# schem2.net
KiCad netlist of a schematic drawn in EAGLE
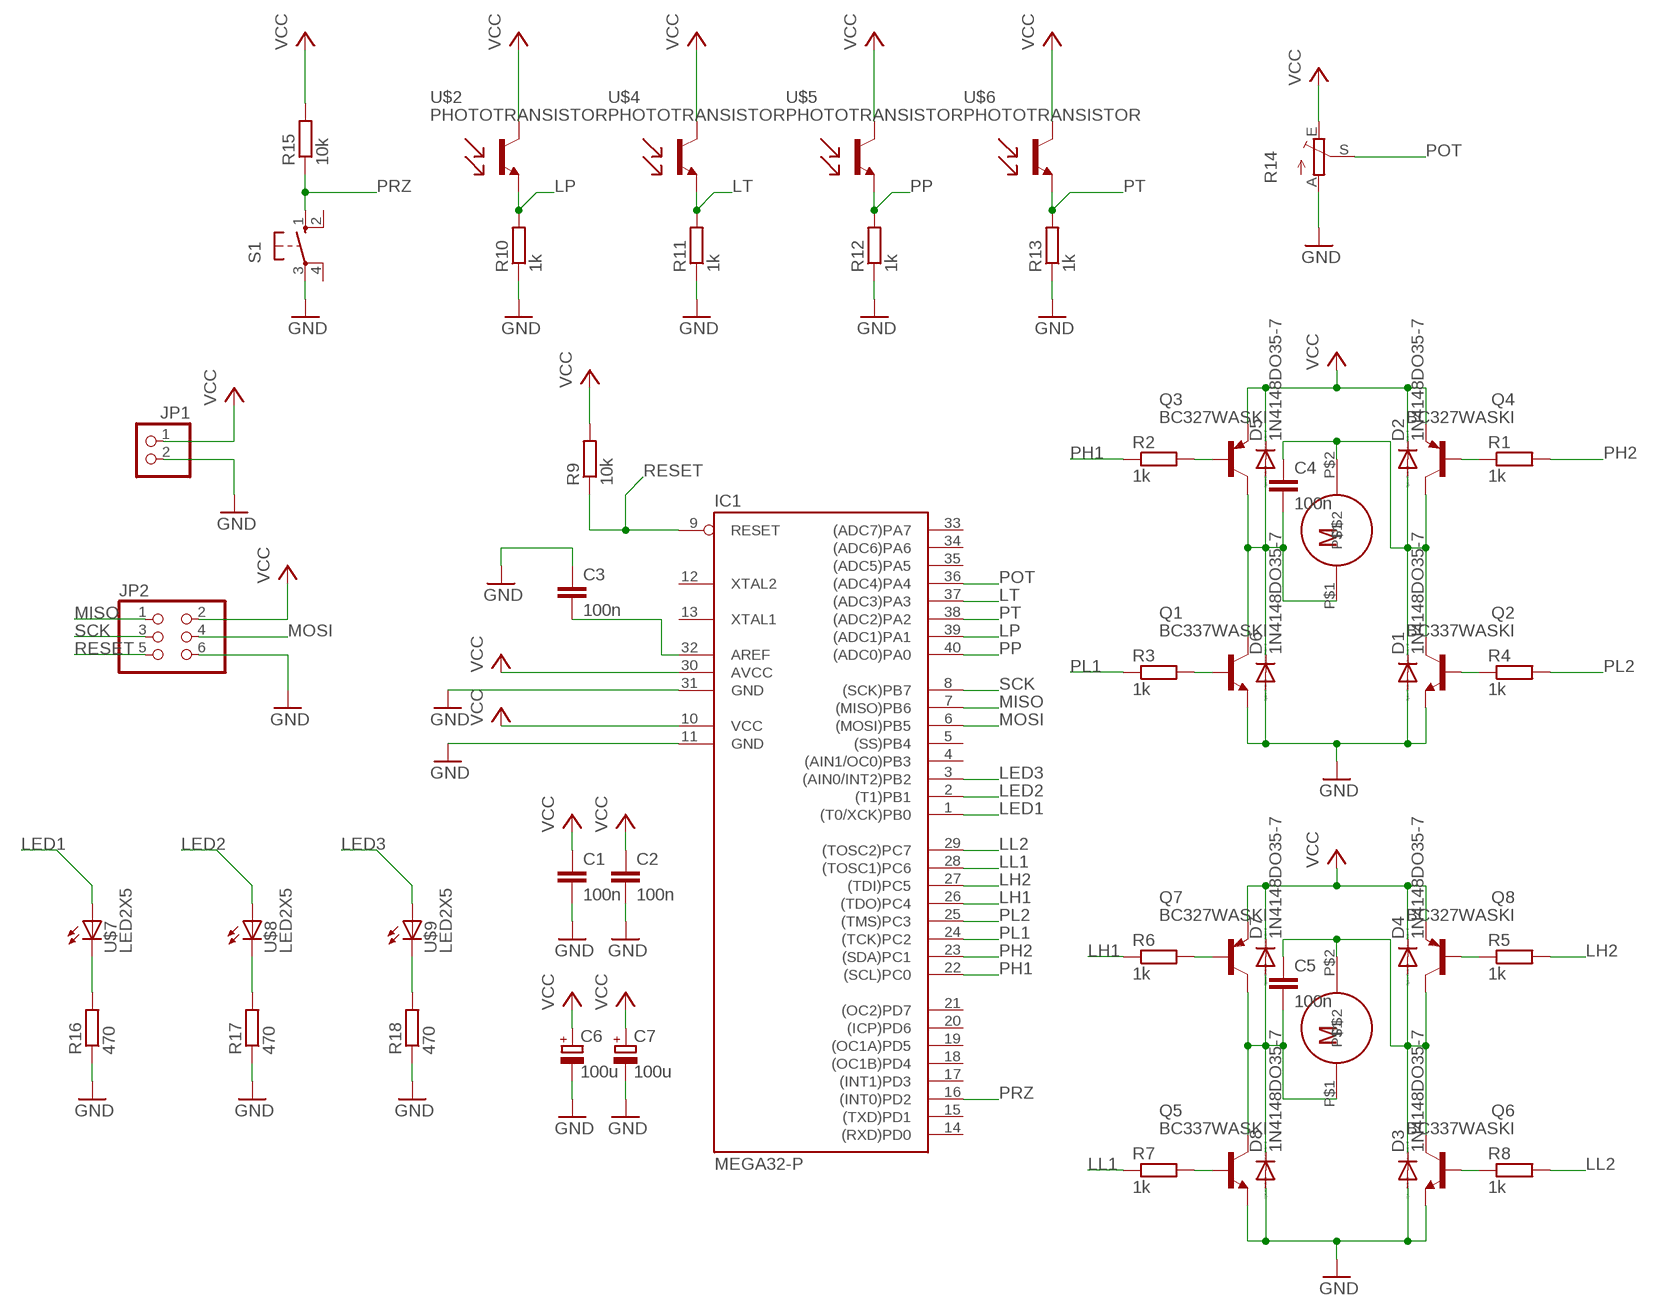
[diagram p0: schematic, sheet 1]

(export (version "E")
  (design (tool "Eeschema 10.0.6"))
  (components
    (comp (ref "C1")
      (value "100n")
      (footprint "eagle-import:C025-025X050")
      (libsource (lib "eagle-import") (part "C-EU025-025X050"))
    )
    (comp (ref "C2")
      (value "100n")
      (footprint "eagle-import:C025-025X050")
      (libsource (lib "eagle-import") (part "C-EU025-025X050"))
    )
    (comp (ref "C3")
      (value "100n")
      (footprint "eagle-import:C025-025X050")
      (libsource (lib "eagle-import") (part "C-EU025-025X050"))
    )
    (comp (ref "C4")
      (value "100n")
      (footprint "eagle-import:C025-025X050")
      (libsource (lib "eagle-import") (part "C-EU025-025X050"))
    )
    (comp (ref "C5")
      (value "100n")
      (footprint "eagle-import:C025-025X050")
      (libsource (lib "eagle-import") (part "C-EU025-025X050"))
    )
    (comp (ref "C6")
      (value "100u")
      (footprint "eagle-import:E2-5")
      (libsource (lib "eagle-import") (part "CPOL-EUE2-5"))
    )
    (comp (ref "C7")
      (value "100u")
      (footprint "eagle-import:E2-5")
      (libsource (lib "eagle-import") (part "CPOL-EUE2-5"))
    )
    (comp (ref "D1")
      (value "1N4148DO35-7")
      (footprint "eagle-import:DO35-7")
      (libsource (lib "eagle-import") (part "1N4148DO35-7"))
    )
    (comp (ref "D2")
      (value "1N4148DO35-7")
      (footprint "eagle-import:DO35-7")
      (libsource (lib "eagle-import") (part "1N4148DO35-7"))
    )
    (comp (ref "D3")
      (value "1N4148DO35-7")
      (footprint "eagle-import:DO35-7")
      (libsource (lib "eagle-import") (part "1N4148DO35-7"))
    )
    (comp (ref "D4")
      (value "1N4148DO35-7")
      (footprint "eagle-import:DO35-7")
      (libsource (lib "eagle-import") (part "1N4148DO35-7"))
    )
    (comp (ref "D5")
      (value "1N4148DO35-7")
      (footprint "eagle-import:DO35-7")
      (libsource (lib "eagle-import") (part "1N4148DO35-7"))
    )
    (comp (ref "D6")
      (value "1N4148DO35-7")
      (footprint "eagle-import:DO35-7")
      (libsource (lib "eagle-import") (part "1N4148DO35-7"))
    )
    (comp (ref "D7")
      (value "1N4148DO35-7")
      (footprint "eagle-import:DO35-7")
      (libsource (lib "eagle-import") (part "1N4148DO35-7"))
    )
    (comp (ref "D8")
      (value "1N4148DO35-7")
      (footprint "eagle-import:DO35-7")
      (libsource (lib "eagle-import") (part "1N4148DO35-7"))
    )
    (comp (ref "IC1")
      (value "MEGA32-P")
      (footprint "eagle-import:DIL40")
      (fields (field (name "MPN") "ATMEGA32-16PU"))
      (libsource (lib "eagle-import") (part "MEGA32-P"))
    )
    (comp (ref "JP1")
      (value "PINHD-1X2")
      (footprint "eagle-import:1X02")
      (libsource (lib "eagle-import") (part "PINHD-1X2"))
    )
    (comp (ref "JP2")
      (value "PINHD-2X3")
      (footprint "eagle-import:2X03")
      (libsource (lib "eagle-import") (part "PINHD-2X3"))
    )
    (comp (ref "Q1")
      (value "BC337WASKI")
      (footprint "eagle-import:TO92-WASKI")
      (libsource (lib "eagle-import") (part "BC337WASKI"))
    )
    (comp (ref "Q2")
      (value "BC337WASKI")
      (footprint "eagle-import:TO92-WASKI")
      (libsource (lib "eagle-import") (part "BC337WASKI"))
    )
    (comp (ref "Q3")
      (value "BC327WASKI")
      (footprint "eagle-import:TO92-WASKI")
      (libsource (lib "eagle-import") (part "BC327WASKI"))
    )
    (comp (ref "Q4")
      (value "BC327WASKI")
      (footprint "eagle-import:TO92-WASKI")
      (libsource (lib "eagle-import") (part "BC327WASKI"))
    )
    (comp (ref "Q5")
      (value "BC337WASKI")
      (footprint "eagle-import:TO92-WASKI")
      (libsource (lib "eagle-import") (part "BC337WASKI"))
    )
    (comp (ref "Q6")
      (value "BC337WASKI")
      (footprint "eagle-import:TO92-WASKI")
      (libsource (lib "eagle-import") (part "BC337WASKI"))
    )
    (comp (ref "Q7")
      (value "BC327WASKI")
      (footprint "eagle-import:TO92-WASKI")
      (libsource (lib "eagle-import") (part "BC327WASKI"))
    )
    (comp (ref "Q8")
      (value "BC327WASKI")
      (footprint "eagle-import:TO92-WASKI")
      (libsource (lib "eagle-import") (part "BC327WASKI"))
    )
    (comp (ref "R1")
      (value "1k")
      (footprint "eagle-import:0207_7")
      (libsource (lib "eagle-import") (part "R-EU_0207/7"))
    )
    (comp (ref "R2")
      (value "1k")
      (footprint "eagle-import:0207_7")
      (libsource (lib "eagle-import") (part "R-EU_0207/7"))
    )
    (comp (ref "R3")
      (value "1k")
      (footprint "eagle-import:0207_7")
      (libsource (lib "eagle-import") (part "R-EU_0207/7"))
    )
    (comp (ref "R4")
      (value "1k")
      (footprint "eagle-import:0207_7")
      (libsource (lib "eagle-import") (part "R-EU_0207/7"))
    )
    (comp (ref "R5")
      (value "1k")
      (footprint "eagle-import:0207_7")
      (libsource (lib "eagle-import") (part "R-EU_0207/7"))
    )
    (comp (ref "R6")
      (value "1k")
      (footprint "eagle-import:0207_7")
      (libsource (lib "eagle-import") (part "R-EU_0207/7"))
    )
    (comp (ref "R7")
      (value "1k")
      (footprint "eagle-import:0207_7")
      (libsource (lib "eagle-import") (part "R-EU_0207/7"))
    )
    (comp (ref "R8")
      (value "1k")
      (footprint "eagle-import:0207_7")
      (libsource (lib "eagle-import") (part "R-EU_0207/7"))
    )
    (comp (ref "R9")
      (value "10k")
      (footprint "eagle-import:0207_7")
      (libsource (lib "eagle-import") (part "R-EU_0207/7"))
    )
    (comp (ref "R10")
      (value "1k")
      (footprint "eagle-import:0207_7")
      (libsource (lib "eagle-import") (part "R-EU_0207/7"))
    )
    (comp (ref "R11")
      (value "1k")
      (footprint "eagle-import:0207_7")
      (libsource (lib "eagle-import") (part "R-EU_0207/7"))
    )
    (comp (ref "R12")
      (value "1k")
      (footprint "eagle-import:0207_7")
      (libsource (lib "eagle-import") (part "R-EU_0207/7"))
    )
    (comp (ref "R13")
      (value "1k")
      (footprint "eagle-import:0207_7")
      (libsource (lib "eagle-import") (part "R-EU_0207/7"))
    )
    (comp (ref "R14")
      (value "TRIM_EU-B64Y")
      (footprint "eagle-import:B64Y")
      (libsource (lib "eagle-import") (part "TRIM_EU-B64Y"))
    )
    (comp (ref "R15")
      (value "10k")
      (footprint "eagle-import:0207_7")
      (libsource (lib "eagle-import") (part "R-EU_0207/7"))
    )
    (comp (ref "R16")
      (value "470")
      (footprint "eagle-import:0207_7")
      (libsource (lib "eagle-import") (part "R-EU_0207/7"))
    )
    (comp (ref "R17")
      (value "470")
      (footprint "eagle-import:0207_7")
      (libsource (lib "eagle-import") (part "R-EU_0207/7"))
    )
    (comp (ref "R18")
      (value "470")
      (footprint "eagle-import:0207_7")
      (libsource (lib "eagle-import") (part "R-EU_0207/7"))
    )
    (comp (ref "S1")
      (value "10-XX")
      (footprint "eagle-import:B3F-10XX")
      (fields (field (name "MPN") "B3F-1000"))
      (libsource (lib "eagle-import") (part "10-XX"))
    )
    (comp (ref "U$1")
      (value "DG02S")
      (footprint "eagle-import:DG02S")
      (libsource (lib "eagle-import") (part "DG02S"))
    )
    (comp (ref "U$2")
      (value "PHOTOTRANSISTOR")
      (footprint "eagle-import:PHOTOTRANSISTOR")
      (libsource (lib "eagle-import") (part "PHOTOTRANSISTOR"))
    )
    (comp (ref "U$3")
      (value "DG02S")
      (footprint "eagle-import:DG02S")
      (libsource (lib "eagle-import") (part "DG02S"))
    )
    (comp (ref "U$4")
      (value "PHOTOTRANSISTOR")
      (footprint "eagle-import:PHOTOTRANSISTOR")
      (libsource (lib "eagle-import") (part "PHOTOTRANSISTOR"))
    )
    (comp (ref "U$5")
      (value "PHOTOTRANSISTOR")
      (footprint "eagle-import:PHOTOTRANSISTOR")
      (libsource (lib "eagle-import") (part "PHOTOTRANSISTOR"))
    )
    (comp (ref "U$6")
      (value "PHOTOTRANSISTOR")
      (footprint "eagle-import:PHOTOTRANSISTOR")
      (libsource (lib "eagle-import") (part "PHOTOTRANSISTOR"))
    )
    (comp (ref "U$7")
      (value "LED2X5")
      (footprint "eagle-import:LED3MM")
      (libsource (lib "eagle-import") (part "LED2X5"))
    )
    (comp (ref "U$8")
      (value "LED2X5")
      (footprint "eagle-import:LED3MM")
      (libsource (lib "eagle-import") (part "LED2X5"))
    )
    (comp (ref "U$9")
      (value "LED2X5")
      (footprint "eagle-import:LED3MM")
      (libsource (lib "eagle-import") (part "LED2X5"))
    )
  )
  (nets
    (net (code "1") (name "/LED1") (class "Default")
      (node (ref "IC1") (pin "1") (pinfunction "(T0/XCK)PB0_1") (pintype "bidirectional"))
      (node (ref "U$7") (pin "A") (pinfunction "A_A") (pintype "passive"))
    )
    (net (code "2") (name "/LED2") (class "Default")
      (node (ref "IC1") (pin "2") (pinfunction "(T1)PB1_2") (pintype "bidirectional"))
      (node (ref "U$8") (pin "A") (pinfunction "A_A") (pintype "passive"))
    )
    (net (code "3") (name "/LED3") (class "Default")
      (node (ref "IC1") (pin "3") (pinfunction "(AIN0/INT2)PB2_3") (pintype "bidirectional"))
      (node (ref "U$9") (pin "A") (pinfunction "A_A") (pintype "passive"))
    )
    (net (code "4") (name "/LH1") (class "Default")
      (node (ref "IC1") (pin "26") (pinfunction "(TDO)PC4_26") (pintype "bidirectional"))
      (node (ref "R6") (pin "1") (pinfunction "1_1") (pintype "passive"))
    )
    (net (code "5") (name "/LH2") (class "Default")
      (node (ref "IC1") (pin "27") (pinfunction "(TDI)PC5_27") (pintype "bidirectional"))
      (node (ref "R5") (pin "2") (pinfunction "2_2") (pintype "passive"))
    )
    (net (code "6") (name "/LL1") (class "Default")
      (node (ref "IC1") (pin "28") (pinfunction "(TOSC1)PC6_28") (pintype "bidirectional"))
      (node (ref "R7") (pin "1") (pinfunction "1_1") (pintype "passive"))
    )
    (net (code "7") (name "/LL2") (class "Default")
      (node (ref "IC1") (pin "29") (pinfunction "(TOSC2)PC7_29") (pintype "bidirectional"))
      (node (ref "R8") (pin "2") (pinfunction "2_2") (pintype "passive"))
    )
    (net (code "8") (name "/LP") (class "Default")
      (node (ref "IC1") (pin "39") (pinfunction "(ADC1)PA1_39") (pintype "bidirectional"))
      (node (ref "R10") (pin "2") (pinfunction "2_2") (pintype "passive"))
      (node (ref "U$2") (pin "E") (pinfunction "E_E") (pintype "passive"))
    )
    (net (code "9") (name "/LT") (class "Default")
      (node (ref "IC1") (pin "37") (pinfunction "(ADC3)PA3_37") (pintype "bidirectional"))
      (node (ref "R11") (pin "2") (pinfunction "2_2") (pintype "passive"))
      (node (ref "U$4") (pin "E") (pinfunction "E_E") (pintype "passive"))
    )
    (net (code "10") (name "/MISO") (class "Default")
      (node (ref "IC1") (pin "7") (pinfunction "(MISO)PB6_7") (pintype "bidirectional"))
      (node (ref "JP2") (pin "1") (pinfunction "1_1") (pintype "passive"))
    )
    (net (code "11") (name "/MOSI") (class "Default")
      (node (ref "IC1") (pin "6") (pinfunction "(MOSI)PB5_6") (pintype "bidirectional"))
      (node (ref "JP2") (pin "4") (pinfunction "4_4") (pintype "passive"))
    )
    (net (code "12") (name "/PH1") (class "Default")
      (node (ref "IC1") (pin "22") (pinfunction "(SCL)PC0_22") (pintype "bidirectional"))
      (node (ref "R2") (pin "1") (pinfunction "1_1") (pintype "passive"))
    )
    (net (code "13") (name "/PH2") (class "Default")
      (node (ref "IC1") (pin "23") (pinfunction "(SDA)PC1_23") (pintype "bidirectional"))
      (node (ref "R1") (pin "2") (pinfunction "2_2") (pintype "passive"))
    )
    (net (code "14") (name "/PL1") (class "Default")
      (node (ref "IC1") (pin "24") (pinfunction "(TCK)PC2_24") (pintype "bidirectional"))
      (node (ref "R3") (pin "1") (pinfunction "1_1") (pintype "passive"))
    )
    (net (code "15") (name "/PL2") (class "Default")
      (node (ref "IC1") (pin "25") (pinfunction "(TMS)PC3_25") (pintype "bidirectional"))
      (node (ref "R4") (pin "2") (pinfunction "2_2") (pintype "passive"))
    )
    (net (code "16") (name "/POT") (class "Default")
      (node (ref "IC1") (pin "36") (pinfunction "(ADC4)PA4_36") (pintype "bidirectional"))
      (node (ref "R14") (pin "S") (pinfunction "S_S") (pintype "passive"))
    )
    (net (code "17") (name "/PP") (class "Default")
      (node (ref "IC1") (pin "40") (pinfunction "(ADC0)PA0_40") (pintype "bidirectional"))
      (node (ref "R12") (pin "2") (pinfunction "2_2") (pintype "passive"))
      (node (ref "U$5") (pin "E") (pinfunction "E_E") (pintype "passive"))
    )
    (net (code "18") (name "/PRZ") (class "Default")
      (node (ref "IC1") (pin "16") (pinfunction "(INT0)PD2_16") (pintype "bidirectional"))
      (node (ref "R15") (pin "1") (pinfunction "1_1") (pintype "passive"))
      (node (ref "S1") (pin "1") (pinfunction "S_1") (pintype "passive"))
    )
    (net (code "19") (name "/PT") (class "Default")
      (node (ref "IC1") (pin "38") (pinfunction "(ADC2)PA2_38") (pintype "bidirectional"))
      (node (ref "R13") (pin "2") (pinfunction "2_2") (pintype "passive"))
      (node (ref "U$6") (pin "E") (pinfunction "E_E") (pintype "passive"))
    )
    (net (code "20") (name "/RESET") (class "Default")
      (node (ref "IC1") (pin "9") (pinfunction "RESET_9") (pintype "input"))
      (node (ref "JP2") (pin "5") (pinfunction "5_5") (pintype "passive"))
      (node (ref "R9") (pin "1") (pinfunction "1_1") (pintype "passive"))
    )
    (net (code "21") (name "/SCK") (class "Default")
      (node (ref "IC1") (pin "8") (pinfunction "(SCK)PB7_8") (pintype "bidirectional"))
      (node (ref "JP2") (pin "3") (pinfunction "3_3") (pintype "passive"))
    )
    (net (code "22") (name "GND") (class "Default")
      (node (ref "C1") (pin "2") (pinfunction "2_2") (pintype "passive"))
      (node (ref "C2") (pin "2") (pinfunction "2_2") (pintype "passive"))
      (node (ref "C3") (pin "1") (pinfunction "1_1") (pintype "passive"))
      (node (ref "C6") (pin "-") (pinfunction "-_-") (pintype "passive"))
      (node (ref "C7") (pin "-") (pinfunction "-_-") (pintype "passive"))
      (node (ref "D1") (pin "A") (pinfunction "A_A") (pintype "passive"))
      (node (ref "D3") (pin "A") (pinfunction "A_A") (pintype "passive"))
      (node (ref "D6") (pin "A") (pinfunction "A_A") (pintype "passive"))
      (node (ref "D8") (pin "A") (pinfunction "A_A") (pintype "passive"))
      (node (ref "IC1") (pin "11") (pinfunction "GND_11") (pintype "power_in"))
      (node (ref "IC1") (pin "31") (pinfunction "GND_31") (pintype "power_in"))
      (node (ref "JP1") (pin "2") (pinfunction "2_2") (pintype "passive"))
      (node (ref "JP2") (pin "6") (pinfunction "6_6") (pintype "passive"))
      (node (ref "Q1") (pin "E") (pinfunction "E_E") (pintype "passive"))
      (node (ref "Q2") (pin "E") (pinfunction "E_E") (pintype "passive"))
      (node (ref "Q5") (pin "E") (pinfunction "E_E") (pintype "passive"))
      (node (ref "Q6") (pin "E") (pinfunction "E_E") (pintype "passive"))
      (node (ref "R10") (pin "1") (pinfunction "1_1") (pintype "passive"))
      (node (ref "R11") (pin "1") (pinfunction "1_1") (pintype "passive"))
      (node (ref "R12") (pin "1") (pinfunction "1_1") (pintype "passive"))
      (node (ref "R13") (pin "1") (pinfunction "1_1") (pintype "passive"))
      (node (ref "R14") (pin "A") (pinfunction "A_A") (pintype "passive"))
      (node (ref "R16") (pin "1") (pinfunction "1_1") (pintype "passive"))
      (node (ref "R17") (pin "1") (pinfunction "1_1") (pintype "passive"))
      (node (ref "R18") (pin "1") (pinfunction "1_1") (pintype "passive"))
      (node (ref "S1") (pin "3") (pinfunction "P_3") (pintype "passive"))
    )
    (net (code "23") (name "Net-(C4-Pad1)") (class "Default")
      (node (ref "C4") (pin "1") (pinfunction "1_1") (pintype "passive"))
      (node (ref "D1") (pin "C") (pinfunction "C_C") (pintype "passive"))
      (node (ref "D2") (pin "A") (pinfunction "A_A") (pintype "passive"))
      (node (ref "Q2") (pin "C") (pinfunction "C_C") (pintype "passive"))
      (node (ref "Q4") (pin "C") (pinfunction "C_C") (pintype "passive"))
      (node (ref "U$1") (pin "P$2") (pinfunction "P$2_P$2") (pintype "bidirectional"))
    )
    (net (code "24") (name "Net-(C4-Pad2)") (class "Default")
      (node (ref "C4") (pin "2") (pinfunction "2_2") (pintype "passive"))
      (node (ref "D5") (pin "A") (pinfunction "A_A") (pintype "passive"))
      (node (ref "D6") (pin "C") (pinfunction "C_C") (pintype "passive"))
      (node (ref "Q1") (pin "C") (pinfunction "C_C") (pintype "passive"))
      (node (ref "Q3") (pin "C") (pinfunction "C_C") (pintype "passive"))
      (node (ref "U$1") (pin "P$1") (pinfunction "P$1_P$1") (pintype "bidirectional"))
    )
    (net (code "25") (name "Net-(C5-Pad1)") (class "Default")
      (node (ref "C5") (pin "1") (pinfunction "1_1") (pintype "passive"))
      (node (ref "D3") (pin "C") (pinfunction "C_C") (pintype "passive"))
      (node (ref "D4") (pin "A") (pinfunction "A_A") (pintype "passive"))
      (node (ref "Q6") (pin "C") (pinfunction "C_C") (pintype "passive"))
      (node (ref "Q8") (pin "C") (pinfunction "C_C") (pintype "passive"))
      (node (ref "U$3") (pin "P$2") (pinfunction "P$2_P$2") (pintype "bidirectional"))
    )
    (net (code "26") (name "Net-(C5-Pad2)") (class "Default")
      (node (ref "C5") (pin "2") (pinfunction "2_2") (pintype "passive"))
      (node (ref "D7") (pin "A") (pinfunction "A_A") (pintype "passive"))
      (node (ref "D8") (pin "C") (pinfunction "C_C") (pintype "passive"))
      (node (ref "Q5") (pin "C") (pinfunction "C_C") (pintype "passive"))
      (node (ref "Q7") (pin "C") (pinfunction "C_C") (pintype "passive"))
      (node (ref "U$3") (pin "P$1") (pinfunction "P$1_P$1") (pintype "bidirectional"))
    )
    (net (code "27") (name "Net-(IC1-AREF)") (class "Default")
      (node (ref "C3") (pin "2") (pinfunction "2_2") (pintype "passive"))
      (node (ref "IC1") (pin "32") (pinfunction "AREF_32") (pintype "passive"))
    )
    (net (code "28") (name "Net-(Q1-PadB)") (class "Default")
      (node (ref "Q1") (pin "B") (pinfunction "B_B") (pintype "passive"))
      (node (ref "R3") (pin "2") (pinfunction "2_2") (pintype "passive"))
    )
    (net (code "29") (name "Net-(Q2-PadB)") (class "Default")
      (node (ref "Q2") (pin "B") (pinfunction "B_B") (pintype "passive"))
      (node (ref "R4") (pin "1") (pinfunction "1_1") (pintype "passive"))
    )
    (net (code "30") (name "Net-(Q3-PadB)") (class "Default")
      (node (ref "Q3") (pin "B") (pinfunction "B_B") (pintype "passive"))
      (node (ref "R2") (pin "2") (pinfunction "2_2") (pintype "passive"))
    )
    (net (code "31") (name "Net-(Q4-PadB)") (class "Default")
      (node (ref "Q4") (pin "B") (pinfunction "B_B") (pintype "passive"))
      (node (ref "R1") (pin "1") (pinfunction "1_1") (pintype "passive"))
    )
    (net (code "32") (name "Net-(Q5-PadB)") (class "Default")
      (node (ref "Q5") (pin "B") (pinfunction "B_B") (pintype "passive"))
      (node (ref "R7") (pin "2") (pinfunction "2_2") (pintype "passive"))
    )
    (net (code "33") (name "Net-(Q6-PadB)") (class "Default")
      (node (ref "Q6") (pin "B") (pinfunction "B_B") (pintype "passive"))
      (node (ref "R8") (pin "1") (pinfunction "1_1") (pintype "passive"))
    )
    (net (code "34") (name "Net-(Q7-PadB)") (class "Default")
      (node (ref "Q7") (pin "B") (pinfunction "B_B") (pintype "passive"))
      (node (ref "R6") (pin "2") (pinfunction "2_2") (pintype "passive"))
    )
    (net (code "35") (name "Net-(Q8-PadB)") (class "Default")
      (node (ref "Q8") (pin "B") (pinfunction "B_B") (pintype "passive"))
      (node (ref "R5") (pin "1") (pinfunction "1_1") (pintype "passive"))
    )
    (net (code "36") (name "Net-(U$7-C)") (class "Default")
      (node (ref "R16") (pin "2") (pinfunction "2_2") (pintype "passive"))
      (node (ref "U$7") (pin "K") (pinfunction "C_K") (pintype "passive"))
    )
    (net (code "37") (name "Net-(U$8-C)") (class "Default")
      (node (ref "R17") (pin "2") (pinfunction "2_2") (pintype "passive"))
      (node (ref "U$8") (pin "K") (pinfunction "C_K") (pintype "passive"))
    )
    (net (code "38") (name "Net-(U$9-C)") (class "Default")
      (node (ref "R18") (pin "2") (pinfunction "2_2") (pintype "passive"))
      (node (ref "U$9") (pin "K") (pinfunction "C_K") (pintype "passive"))
    )
    (net (code "39") (name "VCC") (class "Default")
      (node (ref "C1") (pin "1") (pinfunction "1_1") (pintype "passive"))
      (node (ref "C2") (pin "1") (pinfunction "1_1") (pintype "passive"))
      (node (ref "C6") (pin "+") (pinfunction "+_+") (pintype "passive"))
      (node (ref "C7") (pin "+") (pinfunction "+_+") (pintype "passive"))
      (node (ref "D2") (pin "C") (pinfunction "C_C") (pintype "passive"))
      (node (ref "D4") (pin "C") (pinfunction "C_C") (pintype "passive"))
      (node (ref "D5") (pin "C") (pinfunction "C_C") (pintype "passive"))
      (node (ref "D7") (pin "C") (pinfunction "C_C") (pintype "passive"))
      (node (ref "IC1") (pin "10") (pinfunction "VCC_10") (pintype "power_in"))
      (node (ref "IC1") (pin "30") (pinfunction "AVCC_30") (pintype "power_in"))
      (node (ref "JP1") (pin "1") (pinfunction "1_1") (pintype "passive"))
      (node (ref "JP2") (pin "2") (pinfunction "2_2") (pintype "passive"))
      (node (ref "Q3") (pin "E") (pinfunction "E_E") (pintype "passive"))
      (node (ref "Q4") (pin "E") (pinfunction "E_E") (pintype "passive"))
      (node (ref "Q7") (pin "E") (pinfunction "E_E") (pintype "passive"))
      (node (ref "Q8") (pin "E") (pinfunction "E_E") (pintype "passive"))
      (node (ref "R14") (pin "E") (pinfunction "E_E") (pintype "passive"))
      (node (ref "R15") (pin "2") (pinfunction "2_2") (pintype "passive"))
      (node (ref "R9") (pin "2") (pinfunction "2_2") (pintype "passive"))
      (node (ref "U$2") (pin "C") (pinfunction "C_C") (pintype "passive"))
      (node (ref "U$4") (pin "C") (pinfunction "C_C") (pintype "passive"))
      (node (ref "U$5") (pin "C") (pinfunction "C_C") (pintype "passive"))
      (node (ref "U$6") (pin "C") (pinfunction "C_C") (pintype "passive"))
    )
    (net (code "40") (name "unconnected-(IC1-(ADC5)PA5-Pad35)") (class "Default")
      (node (ref "IC1") (pin "35") (pinfunction "(ADC5)PA5_35") (pintype "bidirectional"))
    )
    (net (code "41") (name "unconnected-(IC1-(ADC6)PA6-Pad34)") (class "Default")
      (node (ref "IC1") (pin "34") (pinfunction "(ADC6)PA6_34") (pintype "bidirectional"))
    )
    (net (code "42") (name "unconnected-(IC1-(ADC7)PA7-Pad33)") (class "Default")
      (node (ref "IC1") (pin "33") (pinfunction "(ADC7)PA7_33") (pintype "bidirectional"))
    )
    (net (code "43") (name "unconnected-(IC1-(AIN1{slash}OC0)PB3-Pad4)") (class "Default")
      (node (ref "IC1") (pin "4") (pinfunction "(AIN1/OC0)PB3_4") (pintype "bidirectional"))
    )
    (net (code "44") (name "unconnected-(IC1-(ICP)PD6-Pad20)") (class "Default")
      (node (ref "IC1") (pin "20") (pinfunction "(ICP)PD6_20") (pintype "bidirectional"))
    )
    (net (code "45") (name "unconnected-(IC1-(INT1)PD3-Pad17)") (class "Default")
      (node (ref "IC1") (pin "17") (pinfunction "(INT1)PD3_17") (pintype "bidirectional"))
    )
    (net (code "46") (name "unconnected-(IC1-(OC1A)PD5-Pad19)") (class "Default")
      (node (ref "IC1") (pin "19") (pinfunction "(OC1A)PD5_19") (pintype "bidirectional"))
    )
    (net (code "47") (name "unconnected-(IC1-(OC1B)PD4-Pad18)") (class "Default")
      (node (ref "IC1") (pin "18") (pinfunction "(OC1B)PD4_18") (pintype "bidirectional"))
    )
    (net (code "48") (name "unconnected-(IC1-(OC2)PD7-Pad21)") (class "Default")
      (node (ref "IC1") (pin "21") (pinfunction "(OC2)PD7_21") (pintype "bidirectional"))
    )
    (net (code "49") (name "unconnected-(IC1-(RXD)PD0-Pad14)") (class "Default")
      (node (ref "IC1") (pin "14") (pinfunction "(RXD)PD0_14") (pintype "bidirectional"))
    )
    (net (code "50") (name "unconnected-(IC1-(SS)PB4-Pad5)") (class "Default")
      (node (ref "IC1") (pin "5") (pinfunction "(SS)PB4_5") (pintype "bidirectional"))
    )
    (net (code "51") (name "unconnected-(IC1-(TXD)PD1-Pad15)") (class "Default")
      (node (ref "IC1") (pin "15") (pinfunction "(TXD)PD1_15") (pintype "bidirectional"))
    )
    (net (code "52") (name "unconnected-(IC1-XTAL1-Pad13)") (class "Default")
      (node (ref "IC1") (pin "13") (pinfunction "XTAL1_13") (pintype "bidirectional"))
    )
    (net (code "53") (name "unconnected-(IC1-XTAL2-Pad12)") (class "Default")
      (node (ref "IC1") (pin "12") (pinfunction "XTAL2_12") (pintype "bidirectional"))
    )
    (net (code "54") (name "unconnected-(S1-P1-Pad4)") (class "Default")
      (node (ref "S1") (pin "4") (pinfunction "P1_4") (pintype "passive"))
    )
    (net (code "55") (name "unconnected-(S1-S1-Pad2)") (class "Default")
      (node (ref "S1") (pin "2") (pinfunction "S1_2") (pintype "passive"))
    )
  )
)
